# SCE.net
KiCad netlist of a schematic drawn in Altium Designer
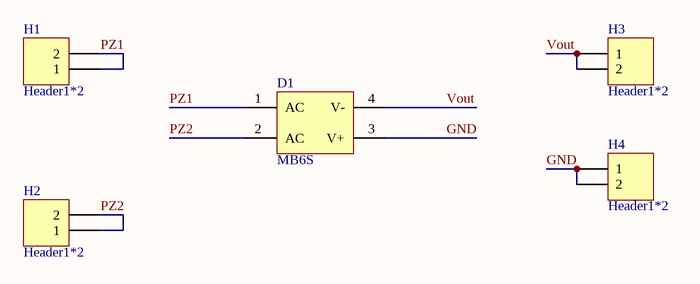
[diagram p0: SCE.SchDoc]

(export (version "E")
  (design (tool "Eeschema 10.0.6"))
  (components
    (comp (ref "D1")
      (value "MB6S")
      (footprint "MB6S")
      (description "Diode Bridge")
      (fields (field (name "PUBLISHER") "Altium Limited"))
      (libsource (lib "Schlib1") (part "MB6S"))
    )
    (comp (ref "H1") (value "Header1*2") (footprint "HDR1X2") (libsource (lib "") (part "Header1*2_1")))
    (comp (ref "H2") (value "Header1*2") (footprint "HDR1X2") (libsource (lib "") (part "Header1*2_1")))
    (comp (ref "H3") (value "Header1*2") (footprint "HDR1X2") (libsource (lib "Schlib1") (part "Header1*2")))
    (comp (ref "H4") (value "Header1*2") (footprint "HDR1X2") (libsource (lib "Schlib1") (part "Header1*2")))
  )
  (nets
    (net (code "1") (name "/GND") (class "Default")
      (node (ref "D1") (pin "3") (pinfunction "V+_3") (pintype "passive"))
      (node (ref "H4") (pin "1") (pinfunction "1_1") (pintype "passive"))
      (node (ref "H4") (pin "2") (pinfunction "2_2") (pintype "passive"))
    )
    (net (code "2") (name "/PZ1") (class "Default")
      (node (ref "D1") (pin "1") (pinfunction "AC_1") (pintype "passive"))
      (node (ref "H1") (pin "1") (pinfunction "1_1") (pintype "passive"))
      (node (ref "H1") (pin "2") (pinfunction "2_2") (pintype "passive"))
    )
    (net (code "3") (name "/PZ2") (class "Default")
      (node (ref "D1") (pin "2") (pinfunction "AC_2") (pintype "passive"))
      (node (ref "H2") (pin "1") (pinfunction "1_1") (pintype "passive"))
      (node (ref "H2") (pin "2") (pinfunction "2_2") (pintype "passive"))
    )
    (net (code "4") (name "/Vout") (class "Default")
      (node (ref "D1") (pin "4") (pinfunction "V-_4") (pintype "passive"))
      (node (ref "H3") (pin "1") (pinfunction "1_1") (pintype "passive"))
      (node (ref "H3") (pin "2") (pinfunction "2_2") (pintype "passive"))
    )
  )
)
